# GSM_LED_Indicators.net
KiCad netlist of a schematic drawn in Altium Designer
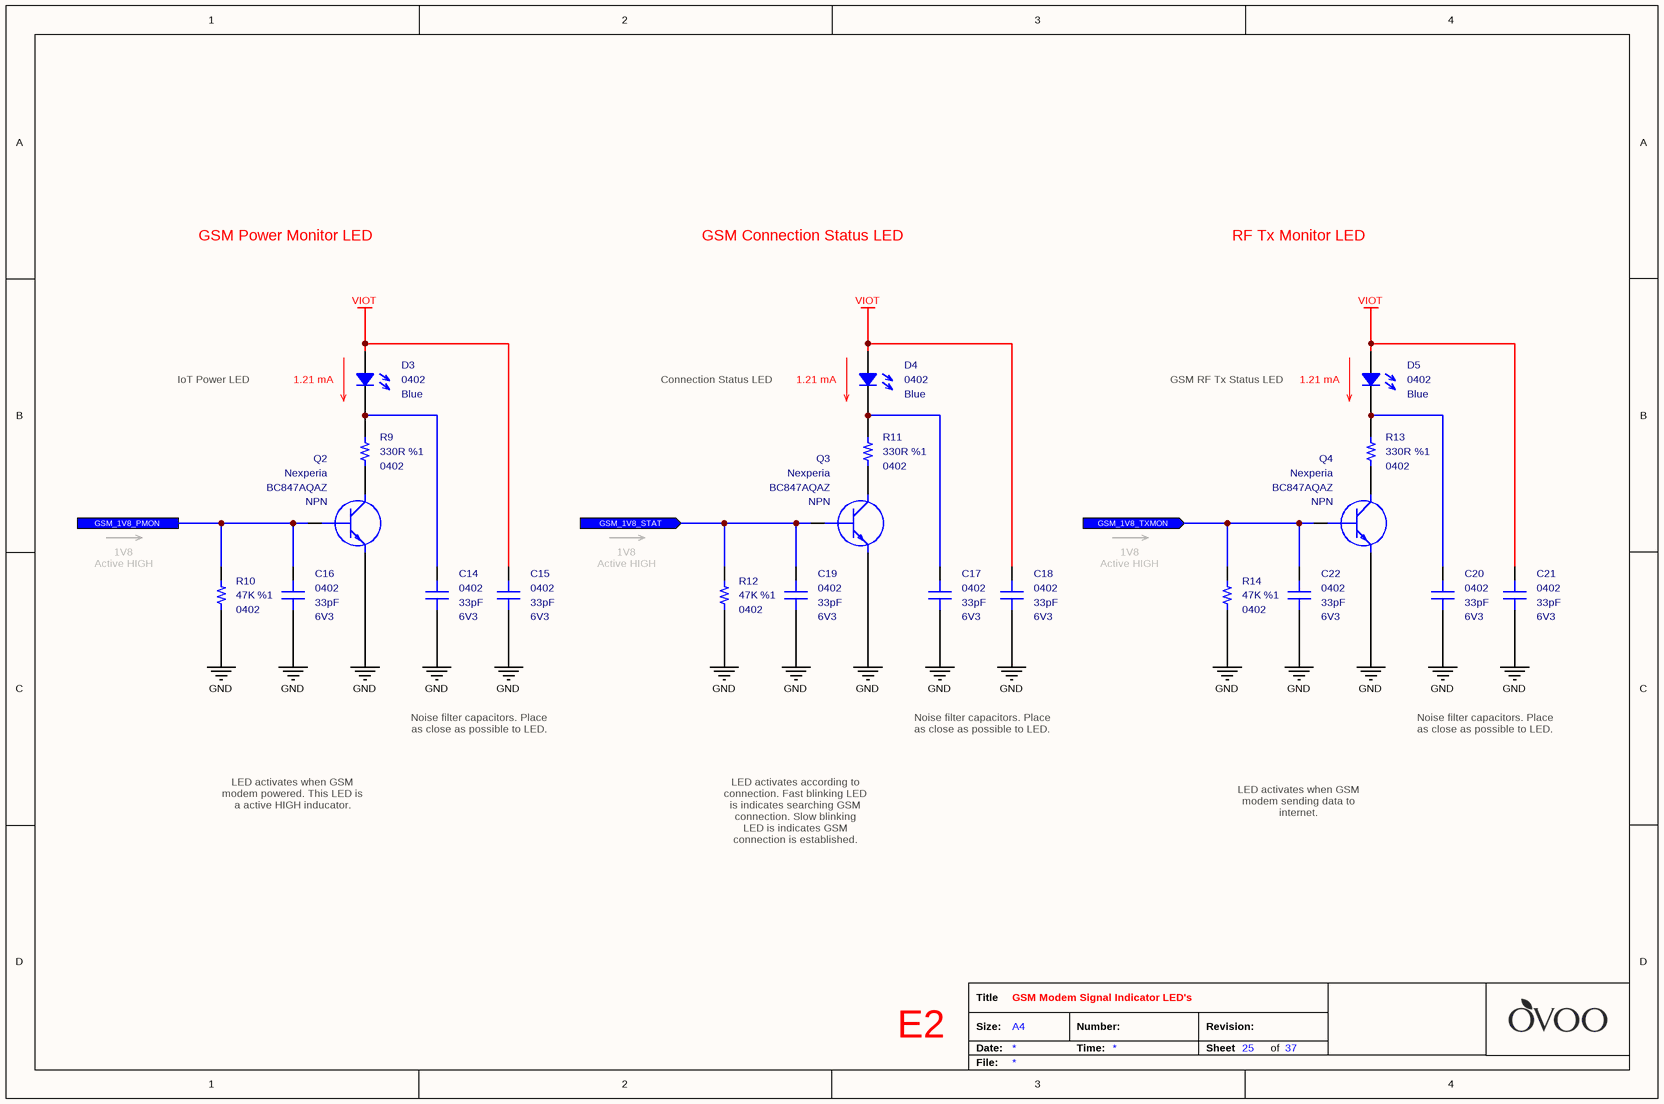
[diagram p0: GSM LED Indicators.SchDoc]

(export (version "E")
  (design (tool "Eeschema 10.0.6"))
  (components
    (comp (ref "C14")
      (value "33pF")
      (footprint "CAPACITOR_0402")
      (description "Capacitor - 33pF [0402] (Ceramic)")
      (fields
        (field (name "MANUFACTURER_PART_NUMBER") "C0402C330J9RACAUTO")
        (field (name "MOUSER_PART_NUMBER") "80-C0402C330J9RAUTO")
        (field (name "CASE") "0402")
        (field (name "VOLTAGE") "6V3")
      )
      (libsource (lib "Ovoo_Schematic") (part "Capacitor - 33pF [0402-6V3]"))
    )
    (comp (ref "C15")
      (value "33pF")
      (footprint "CAPACITOR_0402")
      (description "Capacitor - 33pF [0402] (Ceramic)")
      (fields
        (field (name "MANUFACTURER_PART_NUMBER") "C0402C330J9RACAUTO")
        (field (name "MOUSER_PART_NUMBER") "80-C0402C330J9RAUTO")
        (field (name "CASE") "0402")
        (field (name "VOLTAGE") "6V3")
      )
      (libsource (lib "Ovoo_Schematic") (part "Capacitor - 33pF [0402-6V3]"))
    )
    (comp (ref "C16")
      (value "33pF")
      (footprint "CAPACITOR_0402")
      (description "Capacitor - 33pF [0402] (Ceramic)")
      (fields
        (field (name "MANUFACTURER_PART_NUMBER") "C0402C330J9RACAUTO")
        (field (name "MOUSER_PART_NUMBER") "80-C0402C330J9RAUTO")
        (field (name "CASE") "0402")
        (field (name "VOLTAGE") "6V3")
      )
      (libsource (lib "Ovoo_Schematic") (part "Capacitor - 33pF [0402-6V3]"))
    )
    (comp (ref "C17")
      (value "33pF")
      (footprint "CAPACITOR_0402")
      (description "Capacitor - 33pF [0402] (Ceramic)")
      (fields
        (field (name "MANUFACTURER_PART_NUMBER") "C0402C330J9RACAUTO")
        (field (name "MOUSER_PART_NUMBER") "80-C0402C330J9RAUTO")
        (field (name "CASE") "0402")
        (field (name "VOLTAGE") "6V3")
      )
      (libsource (lib "Ovoo_Schematic") (part "Capacitor - 33pF [0402-6V3]"))
    )
    (comp (ref "C18")
      (value "33pF")
      (footprint "CAPACITOR_0402")
      (description "Capacitor - 33pF [0402] (Ceramic)")
      (fields
        (field (name "MANUFACTURER_PART_NUMBER") "C0402C330J9RACAUTO")
        (field (name "MOUSER_PART_NUMBER") "80-C0402C330J9RAUTO")
        (field (name "CASE") "0402")
        (field (name "VOLTAGE") "6V3")
      )
      (libsource (lib "Ovoo_Schematic") (part "Capacitor - 33pF [0402-6V3]"))
    )
    (comp (ref "C19")
      (value "33pF")
      (footprint "CAPACITOR_0402")
      (description "Capacitor - 33pF [0402] (Ceramic)")
      (fields
        (field (name "MANUFACTURER_PART_NUMBER") "C0402C330J9RACAUTO")
        (field (name "MOUSER_PART_NUMBER") "80-C0402C330J9RAUTO")
        (field (name "CASE") "0402")
        (field (name "VOLTAGE") "6V3")
      )
      (libsource (lib "Ovoo_Schematic") (part "Capacitor - 33pF [0402-6V3]"))
    )
    (comp (ref "C20")
      (value "33pF")
      (footprint "CAPACITOR_0402")
      (description "Capacitor - 33pF [0402] (Ceramic)")
      (fields
        (field (name "MANUFACTURER_PART_NUMBER") "C0402C330J9RACAUTO")
        (field (name "MOUSER_PART_NUMBER") "80-C0402C330J9RAUTO")
        (field (name "CASE") "0402")
        (field (name "VOLTAGE") "6V3")
      )
      (libsource (lib "Ovoo_Schematic") (part "Capacitor - 33pF [0402-6V3]"))
    )
    (comp (ref "C21")
      (value "33pF")
      (footprint "CAPACITOR_0402")
      (description "Capacitor - 33pF [0402] (Ceramic)")
      (fields
        (field (name "MANUFACTURER_PART_NUMBER") "C0402C330J9RACAUTO")
        (field (name "MOUSER_PART_NUMBER") "80-C0402C330J9RAUTO")
        (field (name "CASE") "0402")
        (field (name "VOLTAGE") "6V3")
      )
      (libsource (lib "Ovoo_Schematic") (part "Capacitor - 33pF [0402-6V3]"))
    )
    (comp (ref "C22")
      (value "33pF")
      (footprint "CAPACITOR_0402")
      (description "Capacitor - 33pF [0402] (Ceramic)")
      (fields
        (field (name "MANUFACTURER_PART_NUMBER") "C0402C330J9RACAUTO")
        (field (name "MOUSER_PART_NUMBER") "80-C0402C330J9RAUTO")
        (field (name "CASE") "0402")
        (field (name "VOLTAGE") "6V3")
      )
      (libsource (lib "Ovoo_Schematic") (part "Capacitor - 33pF [0402-6V3]"))
    )
    (comp (ref "D3")
      (value "SMD LED (Blue)")
      (footprint "LED_0402")
      (description "Standard LEDs - SMD PICOLEDTM;BLUE LED; 25M @ 5MA")
      (fields
        (field (name "MANUFACTURER_PART_NUMBER") "SMLP13BC8TT86")
        (field (name "MOUSER_PART_NUMBER") "755-SMLP13BC8TT86")
        (field (name "CASE") "0402")
        (field (name "COLOR") "Blue")
      )
      (libsource (lib "Ovoo_Schematic") (part "Diode - LED (0402-Blue)"))
    )
    (comp (ref "D4")
      (value "SMD LED (Blue)")
      (footprint "LED_0402")
      (description "Standard LEDs - SMD PICOLEDTM;BLUE LED; 25M @ 5MA")
      (fields
        (field (name "MANUFACTURER_PART_NUMBER") "SMLP13BC8TT86")
        (field (name "MOUSER_PART_NUMBER") "755-SMLP13BC8TT86")
        (field (name "CASE") "0402")
        (field (name "COLOR") "Blue")
      )
      (libsource (lib "Ovoo_Schematic") (part "Diode - LED (0402-Blue)"))
    )
    (comp (ref "D5")
      (value "SMD LED (Blue)")
      (footprint "LED_0402")
      (description "Standard LEDs - SMD PICOLEDTM;BLUE LED; 25M @ 5MA")
      (fields
        (field (name "MANUFACTURER_PART_NUMBER") "SMLP13BC8TT86")
        (field (name "MOUSER_PART_NUMBER") "755-SMLP13BC8TT86")
        (field (name "CASE") "0402")
        (field (name "COLOR") "Blue")
      )
      (libsource (lib "Ovoo_Schematic") (part "Diode - LED (0402-Blue)"))
    )
    (comp (ref "Q2")
      (value "Bipolar NPN Transistors")
      (footprint "SOT1215")
      (description "Bipolar Transistors - BJT BC847AQA/DFN1010D-3/REEL 7\" Q2")
      (fields
        (field (name "MOUSER_PART_NUMBER") "771-BC847AQAZ")
        (field (name "MANUFACTURER_NAME") "Nexperia")
        (field (name "MANUFACTURER_PART_NUMBER") "BC847AQAZ")
        (field (name "POLARITY") "NPN")
      )
      (libsource (lib "Ovoo_Schematic") (part "Transistor - BC847"))
    )
    (comp (ref "Q3")
      (value "Bipolar NPN Transistors")
      (footprint "SOT1215")
      (description "Bipolar Transistors - BJT BC847AQA/DFN1010D-3/REEL 7\" Q2")
      (fields
        (field (name "MOUSER_PART_NUMBER") "771-BC847AQAZ")
        (field (name "MANUFACTURER_NAME") "Nexperia")
        (field (name "MANUFACTURER_PART_NUMBER") "BC847AQAZ")
        (field (name "POLARITY") "NPN")
      )
      (libsource (lib "Ovoo_Schematic") (part "Transistor - BC847"))
    )
    (comp (ref "Q4")
      (value "Bipolar NPN Transistors")
      (footprint "SOT1215")
      (description "Bipolar Transistors - BJT BC847AQA/DFN1010D-3/REEL 7\" Q2")
      (fields
        (field (name "MOUSER_PART_NUMBER") "771-BC847AQAZ")
        (field (name "MANUFACTURER_NAME") "Nexperia")
        (field (name "MANUFACTURER_PART_NUMBER") "BC847AQAZ")
        (field (name "POLARITY") "NPN")
      )
      (libsource (lib "Ovoo_Schematic") (part "Transistor - BC847"))
    )
    (comp (ref "R9")
      (value "330R")
      (footprint "RESISTOR_0402")
      (description "Thick Film Resistors - SMD 1/16 W 330 Ohm 1%")
      (fields
        (field (name "MANUFACTURER_PART_NUMBER") "CRCW0402330RFKED")
        (field (name "MOUSER_PART_NUMBER") "71-CRCW0402-330-E3")
        (field (name "TOLERANCE") "%1")
        (field (name "CASE") "0402")
      )
      (libsource (lib "Ovoo_Schematic") (part "Resistor - 330R"))
    )
    (comp (ref "R10")
      (value "47K")
      (footprint "RESISTOR_0402")
      (description "Thick Film Resistors - SMD 1/16 W 47 Kohms 1%")
      (fields
        (field (name "MANUFACTURER_PART_NUMBER") "CRCW040247K0FKED")
        (field (name "MOUSER_PART_NUMBER") "71-CRCW0402-47K-E3")
        (field (name "TOLERANCE") "%1")
        (field (name "CASE") "0402")
      )
      (libsource (lib "Ovoo_Schematic") (part "Resistor - 47K"))
    )
    (comp (ref "R11")
      (value "330R")
      (footprint "RESISTOR_0402")
      (description "Thick Film Resistors - SMD 1/16 W 330 Ohm 1%")
      (fields
        (field (name "MANUFACTURER_PART_NUMBER") "CRCW0402330RFKED")
        (field (name "MOUSER_PART_NUMBER") "71-CRCW0402-330-E3")
        (field (name "TOLERANCE") "%1")
        (field (name "CASE") "0402")
      )
      (libsource (lib "Ovoo_Schematic") (part "Resistor - 330R"))
    )
    (comp (ref "R12")
      (value "47K")
      (footprint "RESISTOR_0402")
      (description "Thick Film Resistors - SMD 1/16 W 47 Kohms 1%")
      (fields
        (field (name "MANUFACTURER_PART_NUMBER") "CRCW040247K0FKED")
        (field (name "MOUSER_PART_NUMBER") "71-CRCW0402-47K-E3")
        (field (name "TOLERANCE") "%1")
        (field (name "CASE") "0402")
      )
      (libsource (lib "Ovoo_Schematic") (part "Resistor - 47K"))
    )
    (comp (ref "R13")
      (value "330R")
      (footprint "RESISTOR_0402")
      (description "Thick Film Resistors - SMD 1/16 W 330 Ohm 1%")
      (fields
        (field (name "MANUFACTURER_PART_NUMBER") "CRCW0402330RFKED")
        (field (name "MOUSER_PART_NUMBER") "71-CRCW0402-330-E3")
        (field (name "TOLERANCE") "%1")
        (field (name "CASE") "0402")
      )
      (libsource (lib "Ovoo_Schematic") (part "Resistor - 330R"))
    )
    (comp (ref "R14")
      (value "47K")
      (footprint "RESISTOR_0402")
      (description "Thick Film Resistors - SMD 1/16 W 47 Kohms 1%")
      (fields
        (field (name "MANUFACTURER_PART_NUMBER") "CRCW040247K0FKED")
        (field (name "MOUSER_PART_NUMBER") "71-CRCW0402-47K-E3")
        (field (name "TOLERANCE") "%1")
        (field (name "CASE") "0402")
      )
      (libsource (lib "Ovoo_Schematic") (part "Resistor - 47K"))
    )
  )
  (nets
    (net (code "1") (name "/GSM_1V8_PMON") (class "Default")
      (node (ref "C16") (pin "1") (pinfunction "1_1") (pintype "passive"))
      (node (ref "Q2") (pin "1") (pinfunction "B_1") (pintype "passive"))
      (node (ref "R10") (pin "2") (pinfunction "2_2") (pintype "passive"))
    )
    (net (code "2") (name "/GSM_1V8_STAT") (class "Default")
      (node (ref "C19") (pin "1") (pinfunction "1_1") (pintype "passive"))
      (node (ref "Q3") (pin "1") (pinfunction "B_1") (pintype "passive"))
      (node (ref "R12") (pin "2") (pinfunction "2_2") (pintype "passive"))
    )
    (net (code "3") (name "/GSM_1V8_TXMON") (class "Default")
      (node (ref "C22") (pin "1") (pinfunction "1_1") (pintype "passive"))
      (node (ref "Q4") (pin "1") (pinfunction "B_1") (pintype "passive"))
      (node (ref "R14") (pin "2") (pinfunction "2_2") (pintype "passive"))
    )
    (net (code "4") (name "GND") (class "Default")
      (node (ref "C14") (pin "2") (pinfunction "2_2") (pintype "passive"))
      (node (ref "C15") (pin "2") (pinfunction "2_2") (pintype "passive"))
      (node (ref "C16") (pin "2") (pinfunction "2_2") (pintype "passive"))
      (node (ref "C17") (pin "2") (pinfunction "2_2") (pintype "passive"))
      (node (ref "C18") (pin "2") (pinfunction "2_2") (pintype "passive"))
      (node (ref "C19") (pin "2") (pinfunction "2_2") (pintype "passive"))
      (node (ref "C20") (pin "2") (pinfunction "2_2") (pintype "passive"))
      (node (ref "C21") (pin "2") (pinfunction "2_2") (pintype "passive"))
      (node (ref "C22") (pin "2") (pinfunction "2_2") (pintype "passive"))
      (node (ref "Q2") (pin "2") (pinfunction "E_2") (pintype "passive"))
      (node (ref "Q3") (pin "2") (pinfunction "E_2") (pintype "passive"))
      (node (ref "Q4") (pin "2") (pinfunction "E_2") (pintype "passive"))
      (node (ref "R10") (pin "1") (pinfunction "1_1") (pintype "passive"))
      (node (ref "R12") (pin "1") (pinfunction "1_1") (pintype "passive"))
      (node (ref "R14") (pin "1") (pinfunction "1_1") (pintype "passive"))
    )
    (net (code "5") (name "Net-(C14-Pad1)") (class "Default")
      (node (ref "C14") (pin "1") (pinfunction "1_1") (pintype "passive"))
      (node (ref "D3") (pin "1") (pinfunction "1_1") (pintype "passive"))
      (node (ref "R9") (pin "2") (pinfunction "2_2") (pintype "passive"))
    )
    (net (code "6") (name "Net-(C17-Pad1)") (class "Default")
      (node (ref "C17") (pin "1") (pinfunction "1_1") (pintype "passive"))
      (node (ref "D4") (pin "1") (pinfunction "1_1") (pintype "passive"))
      (node (ref "R11") (pin "2") (pinfunction "2_2") (pintype "passive"))
    )
    (net (code "7") (name "Net-(C20-Pad1)") (class "Default")
      (node (ref "C20") (pin "1") (pinfunction "1_1") (pintype "passive"))
      (node (ref "D5") (pin "1") (pinfunction "1_1") (pintype "passive"))
      (node (ref "R13") (pin "2") (pinfunction "2_2") (pintype "passive"))
    )
    (net (code "8") (name "Net-(Q2-C)") (class "Default")
      (node (ref "Q2") (pin "3") (pinfunction "C_3") (pintype "passive"))
      (node (ref "R9") (pin "1") (pinfunction "1_1") (pintype "passive"))
    )
    (net (code "9") (name "Net-(Q3-C)") (class "Default")
      (node (ref "Q3") (pin "3") (pinfunction "C_3") (pintype "passive"))
      (node (ref "R11") (pin "1") (pinfunction "1_1") (pintype "passive"))
    )
    (net (code "10") (name "Net-(Q4-C)") (class "Default")
      (node (ref "Q4") (pin "3") (pinfunction "C_3") (pintype "passive"))
      (node (ref "R13") (pin "1") (pinfunction "1_1") (pintype "passive"))
    )
    (net (code "11") (name "VIOT") (class "Default")
      (node (ref "C15") (pin "1") (pinfunction "1_1") (pintype "passive"))
      (node (ref "C18") (pin "1") (pinfunction "1_1") (pintype "passive"))
      (node (ref "C21") (pin "1") (pinfunction "1_1") (pintype "passive"))
      (node (ref "D3") (pin "2") (pinfunction "2_2") (pintype "passive"))
      (node (ref "D4") (pin "2") (pinfunction "2_2") (pintype "passive"))
      (node (ref "D5") (pin "2") (pinfunction "2_2") (pintype "passive"))
    )
  )
)
